# 5xLED.net
KiCad netlist of a schematic drawn in EAGLE
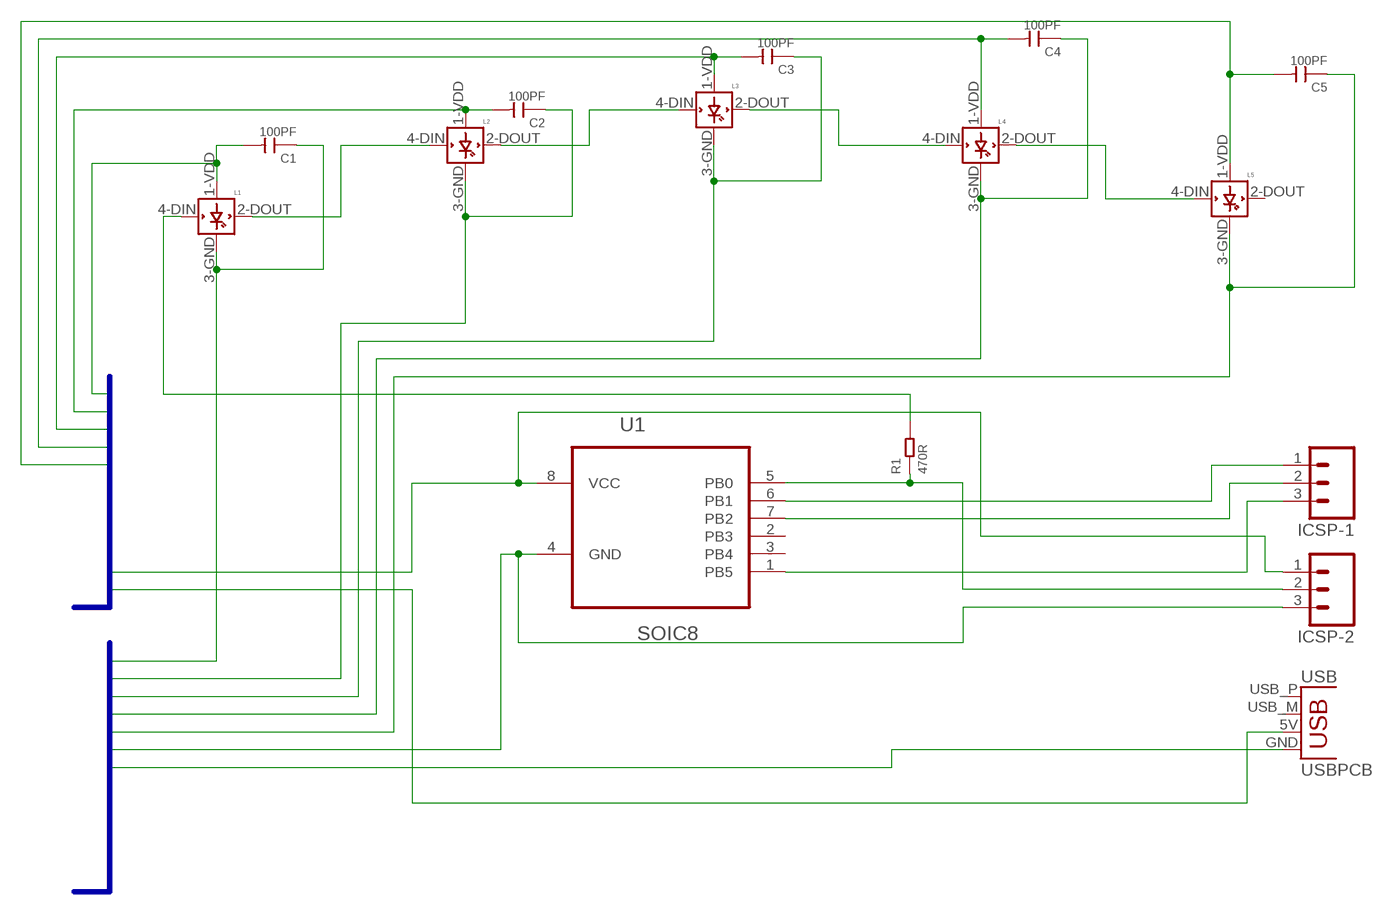
[diagram p0: schematic, sheet 1]

(export (version "E")
  (design (tool "Eeschema 10.0.6"))
  (components
    (comp (ref "C1")
      (value "100PF")
      (footprint "eagle-import:C0805")
      (libsource (lib "eagle-import") (part "CERAMIC-100PF-50V-5%-NPO(0805)"))
    )
    (comp (ref "C2")
      (value "100PF")
      (footprint "eagle-import:C0805")
      (libsource (lib "eagle-import") (part "CERAMIC-100PF-50V-5%-NPO(0805)"))
    )
    (comp (ref "C3")
      (value "100PF")
      (footprint "eagle-import:C0805")
      (libsource (lib "eagle-import") (part "CERAMIC-100PF-50V-5%-NPO(0805)"))
    )
    (comp (ref "C4")
      (value "100PF")
      (footprint "eagle-import:C0805")
      (libsource (lib "eagle-import") (part "CERAMIC-100PF-50V-5%-NPO(0805)"))
    )
    (comp (ref "C5")
      (value "100PF")
      (footprint "eagle-import:C0805")
      (libsource (lib "eagle-import") (part "CERAMIC-100PF-50V-5%-NPO(0805)"))
    )
    (comp (ref "ICSP-1")
      (value "M03SMD_RA_MALE")
      (footprint "eagle-import:1X03_SMD_RA_MALE")
      (libsource (lib "eagle-import") (part "M03SMD_RA_MALE"))
    )
    (comp (ref "ICSP-2")
      (value "M03SMD_RA_MALE")
      (footprint "eagle-import:1X03_SMD_RA_MALE")
      (libsource (lib "eagle-import") (part "M03SMD_RA_MALE"))
    )
    (comp (ref "L1")
      (value "WS2812B")
      (footprint "eagle-import:WS2812B")
      (libsource (lib "eagle-import") (part "WS2812B"))
    )
    (comp (ref "L2")
      (value "WS2812B")
      (footprint "eagle-import:WS2812B")
      (libsource (lib "eagle-import") (part "WS2812B"))
    )
    (comp (ref "L3")
      (value "WS2812B")
      (footprint "eagle-import:WS2812B")
      (libsource (lib "eagle-import") (part "WS2812B"))
    )
    (comp (ref "L4")
      (value "WS2812B")
      (footprint "eagle-import:WS2812B")
      (libsource (lib "eagle-import") (part "WS2812B"))
    )
    (comp (ref "L5")
      (value "WS2812B")
      (footprint "eagle-import:WS2812B")
      (libsource (lib "eagle-import") (part "WS2812B"))
    )
    (comp (ref "R1")
      (value "470R")
      (footprint "eagle-import:R0805")
      (fields (field (name "MPN") "RC0805FR-07470RL"))
      (libsource (lib "eagle-import") (part "SMD-RES-470R-1%-1/8W(0805)"))
    )
    (comp (ref "U1")
      (value "SOIC8")
      (footprint "eagle-import:SOIC8-1.27-5.3X5.3MM")
      (fields (field (name "MPN") "ATTINY85-20SU"))
      (libsource (lib "eagle-import") (part "MCU-ATTINY85-20SU(SOIC8)"))
    )
    (comp (ref "USB")
      (value "USBPCB")
      (footprint "eagle-import:USB-A-PCB")
      (libsource (lib "eagle-import") (part "USBPCB"))
    )
  )
  (nets
    (net (code "1") (name "/GND") (class "Default")
      (node (ref "C1") (pin "1") (pinfunction "1_1") (pintype "passive"))
      (node (ref "C2") (pin "1") (pinfunction "1_1") (pintype "passive"))
      (node (ref "C3") (pin "1") (pinfunction "1_1") (pintype "passive"))
      (node (ref "C4") (pin "1") (pinfunction "1_1") (pintype "passive"))
      (node (ref "C5") (pin "1") (pinfunction "1_1") (pintype "passive"))
      (node (ref "ICSP-2") (pin "3") (pinfunction "3_3") (pintype "passive"))
      (node (ref "L1") (pin "3-GND") (pinfunction "GND_3-GND") (pintype "bidirectional"))
      (node (ref "L2") (pin "3-GND") (pinfunction "GND_3-GND") (pintype "bidirectional"))
      (node (ref "L3") (pin "3-GND") (pinfunction "GND_3-GND") (pintype "bidirectional"))
      (node (ref "L4") (pin "3-GND") (pinfunction "GND_3-GND") (pintype "bidirectional"))
      (node (ref "L5") (pin "3-GND") (pinfunction "GND_3-GND") (pintype "bidirectional"))
      (node (ref "U1") (pin "4") (pinfunction "GND_4") (pintype "passive"))
      (node (ref "USB") (pin "GND") (pinfunction "GND_GND") (pintype "bidirectional"))
    )
    (net (code "2") (name "/VCC") (class "Default")
      (node (ref "C1") (pin "2") (pinfunction "2_2") (pintype "passive"))
      (node (ref "C2") (pin "2") (pinfunction "2_2") (pintype "passive"))
      (node (ref "C3") (pin "2") (pinfunction "2_2") (pintype "passive"))
      (node (ref "C4") (pin "2") (pinfunction "2_2") (pintype "passive"))
      (node (ref "C5") (pin "2") (pinfunction "2_2") (pintype "passive"))
      (node (ref "ICSP-2") (pin "1") (pinfunction "1_1") (pintype "passive"))
      (node (ref "L1") (pin "1-VDD") (pinfunction "VDD_1-VDD") (pintype "bidirectional"))
      (node (ref "L2") (pin "1-VDD") (pinfunction "VDD_1-VDD") (pintype "bidirectional"))
      (node (ref "L3") (pin "1-VDD") (pinfunction "VDD_1-VDD") (pintype "bidirectional"))
      (node (ref "L4") (pin "1-VDD") (pinfunction "VDD_1-VDD") (pintype "bidirectional"))
      (node (ref "L5") (pin "1-VDD") (pinfunction "VDD_1-VDD") (pintype "bidirectional"))
      (node (ref "U1") (pin "8") (pinfunction "VCC_8") (pintype "power_in"))
      (node (ref "USB") (pin "5V") (pinfunction "VBUS_5V") (pintype "bidirectional"))
    )
    (net (code "3") (name "Net-(L1-DIN)") (class "Default")
      (node (ref "L1") (pin "4-DIN") (pinfunction "DIN_4-DIN") (pintype "input"))
      (node (ref "R1") (pin "2") (pinfunction "2_2") (pintype "passive"))
    )
    (net (code "4") (name "Net-(L1-DOUT)") (class "Default")
      (node (ref "L1") (pin "2-DOUT") (pinfunction "DOUT_2-DOUT") (pintype "output"))
      (node (ref "L2") (pin "4-DIN") (pinfunction "DIN_4-DIN") (pintype "input"))
    )
    (net (code "5") (name "Net-(L2-DOUT)") (class "Default")
      (node (ref "L2") (pin "2-DOUT") (pinfunction "DOUT_2-DOUT") (pintype "output"))
      (node (ref "L3") (pin "4-DIN") (pinfunction "DIN_4-DIN") (pintype "input"))
    )
    (net (code "6") (name "Net-(L3-DOUT)") (class "Default")
      (node (ref "L3") (pin "2-DOUT") (pinfunction "DOUT_2-DOUT") (pintype "output"))
      (node (ref "L4") (pin "4-DIN") (pinfunction "DIN_4-DIN") (pintype "input"))
    )
    (net (code "7") (name "Net-(L4-DOUT)") (class "Default")
      (node (ref "L4") (pin "2-DOUT") (pinfunction "DOUT_2-DOUT") (pintype "output"))
      (node (ref "L5") (pin "4-DIN") (pinfunction "DIN_4-DIN") (pintype "input"))
    )
    (net (code "8") (name "Net-(U1-PB0)") (class "Default")
      (node (ref "ICSP-2") (pin "2") (pinfunction "2_2") (pintype "passive"))
      (node (ref "R1") (pin "1") (pinfunction "1_1") (pintype "passive"))
      (node (ref "U1") (pin "5") (pinfunction "PB0_5") (pintype "bidirectional"))
    )
    (net (code "9") (name "Net-(U1-PB1)") (class "Default")
      (node (ref "ICSP-1") (pin "1") (pinfunction "1_1") (pintype "passive"))
      (node (ref "U1") (pin "6") (pinfunction "PB1_6") (pintype "bidirectional"))
    )
    (net (code "10") (name "Net-(U1-PB2)") (class "Default")
      (node (ref "ICSP-1") (pin "2") (pinfunction "2_2") (pintype "passive"))
      (node (ref "U1") (pin "7") (pinfunction "PB2_7") (pintype "bidirectional"))
    )
    (net (code "11") (name "Net-(U1-PB5)") (class "Default")
      (node (ref "ICSP-1") (pin "3") (pinfunction "3_3") (pintype "passive"))
      (node (ref "U1") (pin "1") (pinfunction "PB5_1") (pintype "bidirectional"))
    )
    (net (code "12") (name "unconnected-(L5-DOUT-Pad2-DOUT)") (class "Default")
      (node (ref "L5") (pin "2-DOUT") (pinfunction "DOUT_2-DOUT") (pintype "output"))
    )
    (net (code "13") (name "unconnected-(U1-PB3-Pad2)") (class "Default")
      (node (ref "U1") (pin "2") (pinfunction "PB3_2") (pintype "bidirectional"))
    )
    (net (code "14") (name "unconnected-(U1-PB4-Pad3)") (class "Default")
      (node (ref "U1") (pin "3") (pinfunction "PB4_3") (pintype "bidirectional"))
    )
    (net (code "15") (name "unconnected-(USB-D+-PadUSB_P)") (class "Default")
      (node (ref "USB") (pin "USB_P") (pinfunction "D+_USB_P") (pintype "bidirectional"))
    )
    (net (code "16") (name "unconnected-(USB-D--PadUSB_M)") (class "Default")
      (node (ref "USB") (pin "USB_M") (pinfunction "D-_USB_M") (pintype "bidirectional"))
    )
  )
)
